# Grove-Gas_Sensor_v1_4.net
KiCad netlist of a schematic drawn in EAGLE
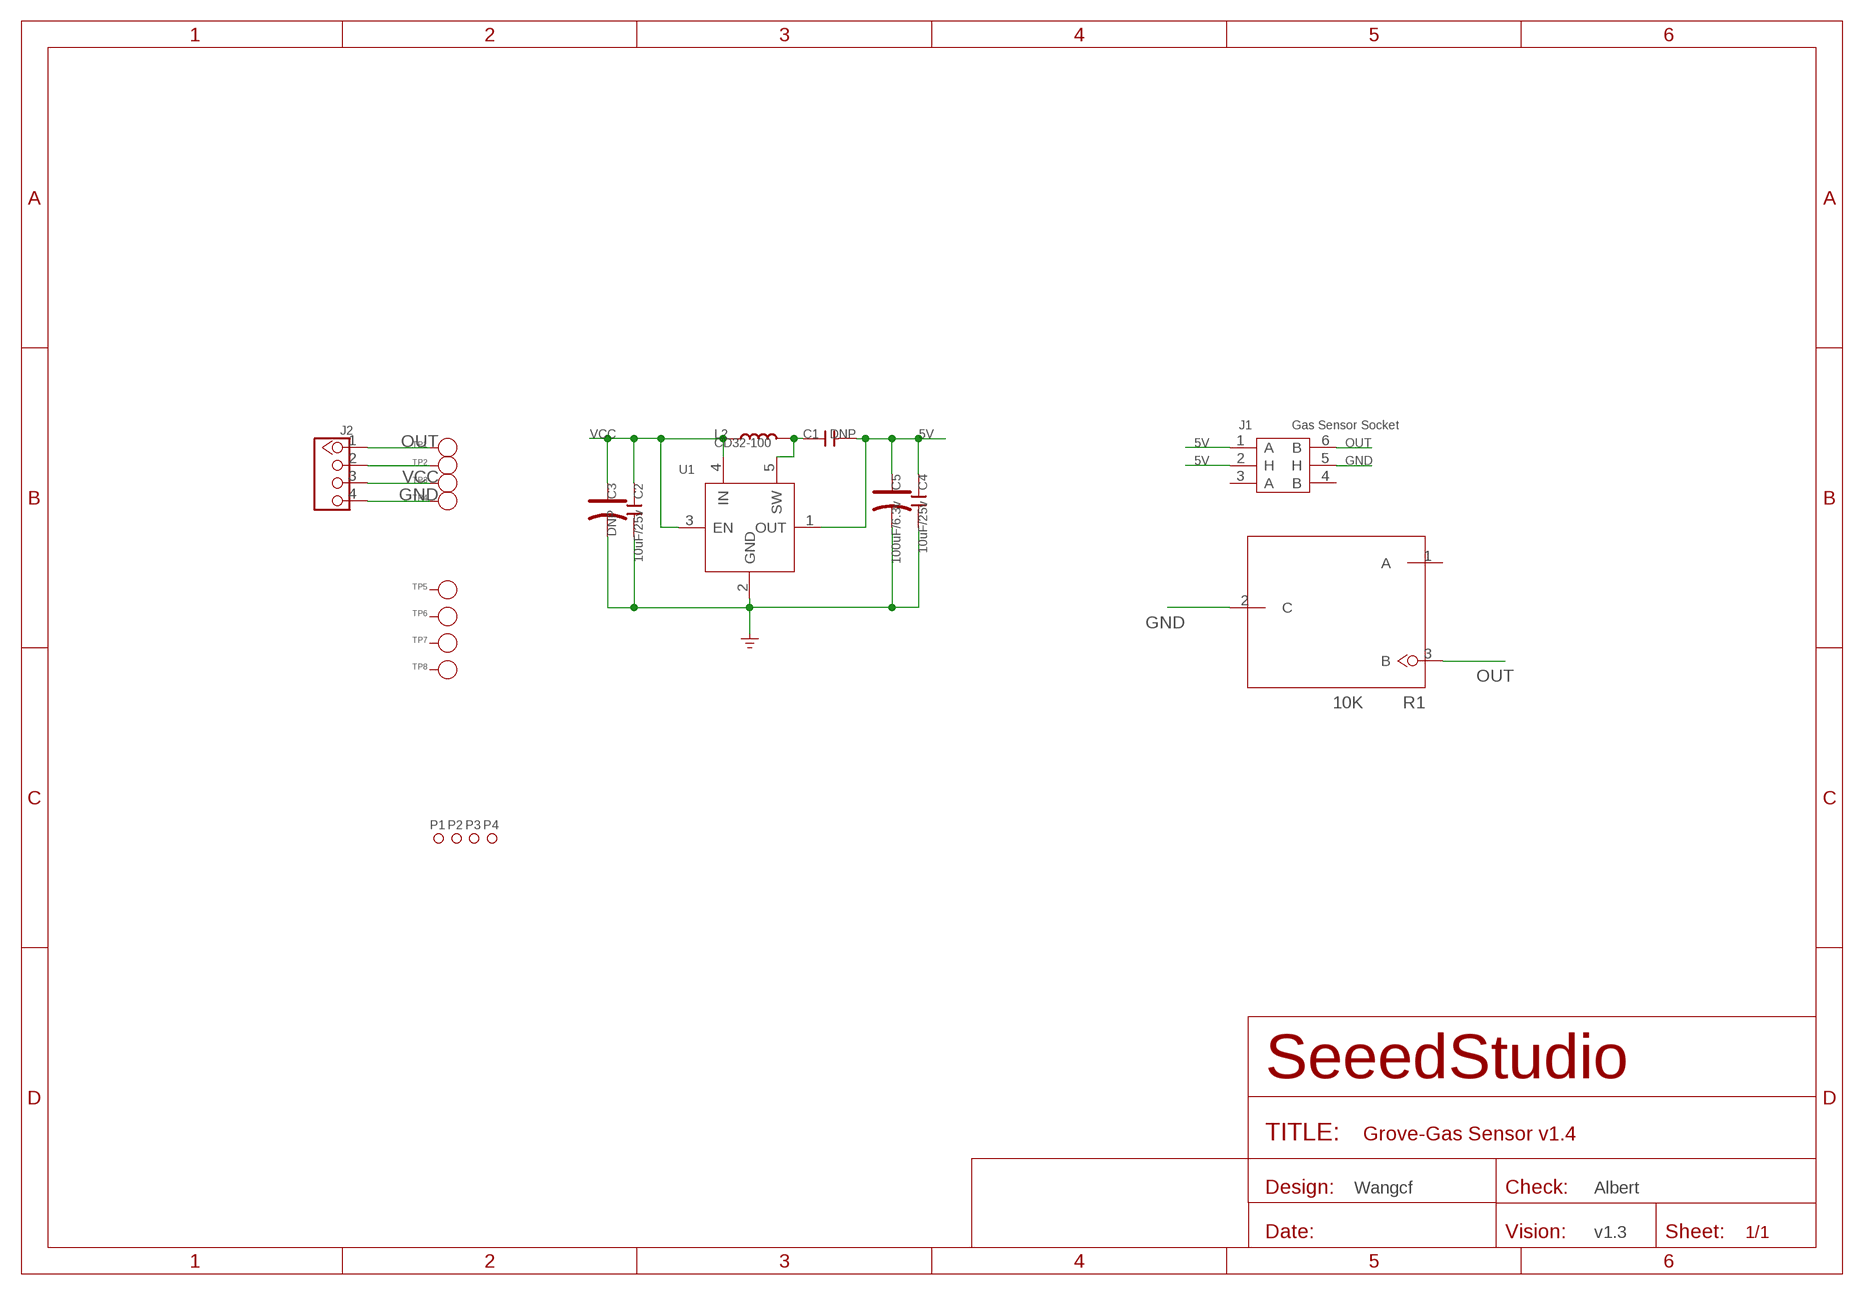
[diagram p0: schematic, sheet 1]

(export (version "E")
  (design (tool "Eeschema 10.0.6"))
  (components
    (comp (ref "C1")
      (value "DNP")
      (footprint "eagle-import:C0603")
      (libsource (lib "eagle-import") (part "C-0603"))
    )
    (comp (ref "C2")
      (value "10uF/25v")
      (footprint "eagle-import:C0805")
      (libsource (lib "eagle-import") (part "C-0805"))
    )
    (comp (ref "C3")
      (value "DNP")
      (footprint "eagle-import:AVX-A")
      (libsource (lib "eagle-import") (part "CAP-AVX-A"))
    )
    (comp (ref "C4")
      (value "10uF/25v")
      (footprint "eagle-import:C0805")
      (libsource (lib "eagle-import") (part "C-0805"))
    )
    (comp (ref "C5")
      (value "100uF/6.3v")
      (footprint "eagle-import:AVX-B")
      (libsource (lib "eagle-import") (part "CAP-AVX-B"))
    )
    (comp (ref "J1")
      (value "Gas Sensor Socket")
      (footprint "eagle-import:6P-D17.6X9.8H")
      (libsource (lib "eagle-import") (part "MQ-SOCKET"))
    )
    (comp (ref "J2")
      (value "TWIG-2.0-LEADED")
      (footprint "eagle-import:4P-LEADED-2.0")
      (libsource (lib "eagle-import") (part "TWIG-2.0-LEADED"))
    )
    (comp (ref "L2")
      (value "CD32-100")
      (footprint "eagle-import:SD32-4R7MC")
      (libsource (lib "eagle-import") (part "CD32'4R7'"))
    )
    (comp (ref "P1")
      (value "PAD-MARK'ANNULAR'")
      (footprint "eagle-import:ROUND-MARK-1.0")
      (fields (field (name "PARTNO") "DNP"))
      (libsource (lib "eagle-import") (part "PAD-MARK'ANNULAR'"))
    )
    (comp (ref "P2")
      (value "PAD-MARK'ANNULAR'")
      (footprint "eagle-import:ROUND-MARK-1.0")
      (fields (field (name "PARTNO") "DNP"))
      (libsource (lib "eagle-import") (part "PAD-MARK'ANNULAR'"))
    )
    (comp (ref "P3")
      (value "PAD-MARK'ANNULAR'")
      (footprint "eagle-import:ROUND-MARK-1.0")
      (fields (field (name "PARTNO") "DNP"))
      (libsource (lib "eagle-import") (part "PAD-MARK'ANNULAR'"))
    )
    (comp (ref "P4")
      (value "PAD-MARK'ANNULAR'")
      (footprint "eagle-import:ROUND-MARK-1.0")
      (fields (field (name "PARTNO") "DNP"))
      (libsource (lib "eagle-import") (part "PAD-MARK'ANNULAR'"))
    )
    (comp (ref "R1")
      (value "10K")
      (footprint "eagle-import:PACKAGE__RESISTANCE")
      (libsource (lib "eagle-import") (part "DEVICE_RESISTANCE"))
    )
    (comp (ref "TP1")
      (value "PAD-TEST-POINT'4545'")
      (footprint "eagle-import:TP_4545")
      (fields (field (name "PARTNO") "DNP"))
      (libsource (lib "eagle-import") (part "PAD-TEST-POINT'4545'"))
    )
    (comp (ref "TP2")
      (value "PAD-TEST-POINT'4545'")
      (footprint "eagle-import:TP_4545")
      (fields (field (name "PARTNO") "DNP"))
      (libsource (lib "eagle-import") (part "PAD-TEST-POINT'4545'"))
    )
    (comp (ref "TP3")
      (value "PAD-TEST-POINT'4545'")
      (footprint "eagle-import:TP_4545")
      (fields (field (name "PARTNO") "DNP"))
      (libsource (lib "eagle-import") (part "PAD-TEST-POINT'4545'"))
    )
    (comp (ref "TP4")
      (value "PAD-TEST-POINT'4545'")
      (footprint "eagle-import:TP_4545")
      (fields (field (name "PARTNO") "DNP"))
      (libsource (lib "eagle-import") (part "PAD-TEST-POINT'4545'"))
    )
    (comp (ref "TP5")
      (value "PAD-TEST-POINT'4545'")
      (footprint "eagle-import:TP_4545")
      (fields (field (name "PARTNO") "DNP"))
      (libsource (lib "eagle-import") (part "PAD-TEST-POINT'4545'"))
    )
    (comp (ref "TP6")
      (value "PAD-TEST-POINT'4545'")
      (footprint "eagle-import:TP_4545")
      (fields (field (name "PARTNO") "DNP"))
      (libsource (lib "eagle-import") (part "PAD-TEST-POINT'4545'"))
    )
    (comp (ref "TP7")
      (value "PAD-TEST-POINT'4545'")
      (footprint "eagle-import:TP_4545")
      (fields (field (name "PARTNO") "DNP"))
      (libsource (lib "eagle-import") (part "PAD-TEST-POINT'4545'"))
    )
    (comp (ref "TP8")
      (value "PAD-TEST-POINT'4545'")
      (footprint "eagle-import:TP_4545")
      (fields (field (name "PARTNO") "DNP"))
      (libsource (lib "eagle-import") (part "PAD-TEST-POINT'4545'"))
    )
    (comp (ref "U1")
      (value "ETA1036")
      (footprint "eagle-import:SOT23-5")
      (libsource (lib "eagle-import") (part "ETA1036"))
    )
  )
  (nets
    (net (code "1") (name "/5V") (class "Default")
      (node (ref "C1") (pin "2") (pinfunction "2_2") (pintype "passive"))
      (node (ref "C4") (pin "1") (pinfunction "1_1") (pintype "passive"))
      (node (ref "C5") (pin "+") (pinfunction "+_+") (pintype "passive"))
      (node (ref "J1") (pin "1") (pinfunction "A_1") (pintype "bidirectional"))
      (node (ref "J1") (pin "2") (pinfunction "H_2") (pintype "bidirectional"))
      (node (ref "U1") (pin "1") (pinfunction "OUT_1") (pintype "bidirectional"))
    )
    (net (code "2") (name "/OUT") (class "Default")
      (node (ref "J1") (pin "6") (pinfunction "B_6") (pintype "bidirectional"))
      (node (ref "J2") (pin "1") (pinfunction "1_1") (pintype "bidirectional"))
      (node (ref "R1") (pin "3") (pinfunction "B_3") (pintype "bidirectional"))
      (node (ref "TP1") (pin "T") (pinfunction "T_T") (pintype "bidirectional"))
    )
    (net (code "3") (name "/VCC") (class "Default")
      (node (ref "C2") (pin "1") (pinfunction "1_1") (pintype "passive"))
      (node (ref "C3") (pin "+") (pinfunction "+_+") (pintype "passive"))
      (node (ref "J2") (pin "3") (pinfunction "3_3") (pintype "bidirectional"))
      (node (ref "L2") (pin "1") (pinfunction "1_1") (pintype "passive"))
      (node (ref "TP3") (pin "T") (pinfunction "T_T") (pintype "bidirectional"))
      (node (ref "U1") (pin "3") (pinfunction "EN_3") (pintype "bidirectional"))
      (node (ref "U1") (pin "4") (pinfunction "IN_4") (pintype "bidirectional"))
    )
    (net (code "4") (name "GND_POWER") (class "Default")
      (node (ref "C2") (pin "2") (pinfunction "2_2") (pintype "passive"))
      (node (ref "C3") (pin "-") (pinfunction "-_-") (pintype "passive"))
      (node (ref "C4") (pin "2") (pinfunction "2_2") (pintype "passive"))
      (node (ref "C5") (pin "-") (pinfunction "-_-") (pintype "passive"))
      (node (ref "J1") (pin "5") (pinfunction "H_5") (pintype "bidirectional"))
      (node (ref "J2") (pin "4") (pinfunction "4_4") (pintype "bidirectional"))
      (node (ref "R1") (pin "2") (pinfunction "C_2") (pintype "bidirectional"))
      (node (ref "TP4") (pin "T") (pinfunction "T_T") (pintype "bidirectional"))
      (node (ref "U1") (pin "2") (pinfunction "GND_2") (pintype "bidirectional"))
    )
    (net (code "5") (name "Net-(J2-Pad2)") (class "Default")
      (node (ref "J2") (pin "2") (pinfunction "2_2") (pintype "bidirectional"))
      (node (ref "TP2") (pin "T") (pinfunction "T_T") (pintype "bidirectional"))
    )
    (net (code "6") (name "Net-(U1-SW)") (class "Default")
      (node (ref "C1") (pin "1") (pinfunction "1_1") (pintype "passive"))
      (node (ref "L2") (pin "2") (pinfunction "2_2") (pintype "passive"))
      (node (ref "U1") (pin "5") (pinfunction "SW_5") (pintype "bidirectional"))
    )
    (net (code "7") (name "unconnected-(J1-A-Pad3)") (class "Default")
      (node (ref "J1") (pin "3") (pinfunction "A_3") (pintype "bidirectional"))
    )
    (net (code "8") (name "unconnected-(J1-B-Pad4)") (class "Default")
      (node (ref "J1") (pin "4") (pinfunction "B_4") (pintype "bidirectional"))
    )
    (net (code "9") (name "unconnected-(R1-A-Pad1)") (class "Default")
      (node (ref "R1") (pin "1") (pinfunction "A_1") (pintype "bidirectional"))
    )
    (net (code "10") (name "unconnected-(TP5-PadT)") (class "Default")
      (node (ref "TP5") (pin "T") (pinfunction "T_T") (pintype "bidirectional"))
    )
    (net (code "11") (name "unconnected-(TP6-PadT)") (class "Default")
      (node (ref "TP6") (pin "T") (pinfunction "T_T") (pintype "bidirectional"))
    )
    (net (code "12") (name "unconnected-(TP7-PadT)") (class "Default")
      (node (ref "TP7") (pin "T") (pinfunction "T_T") (pintype "bidirectional"))
    )
    (net (code "13") (name "unconnected-(TP8-PadT)") (class "Default")
      (node (ref "TP8") (pin "T") (pinfunction "T_T") (pintype "bidirectional"))
    )
  )
)
